# THREE_PHASE_METER.net
KiCad netlist of a schematic drawn in Altium Designer
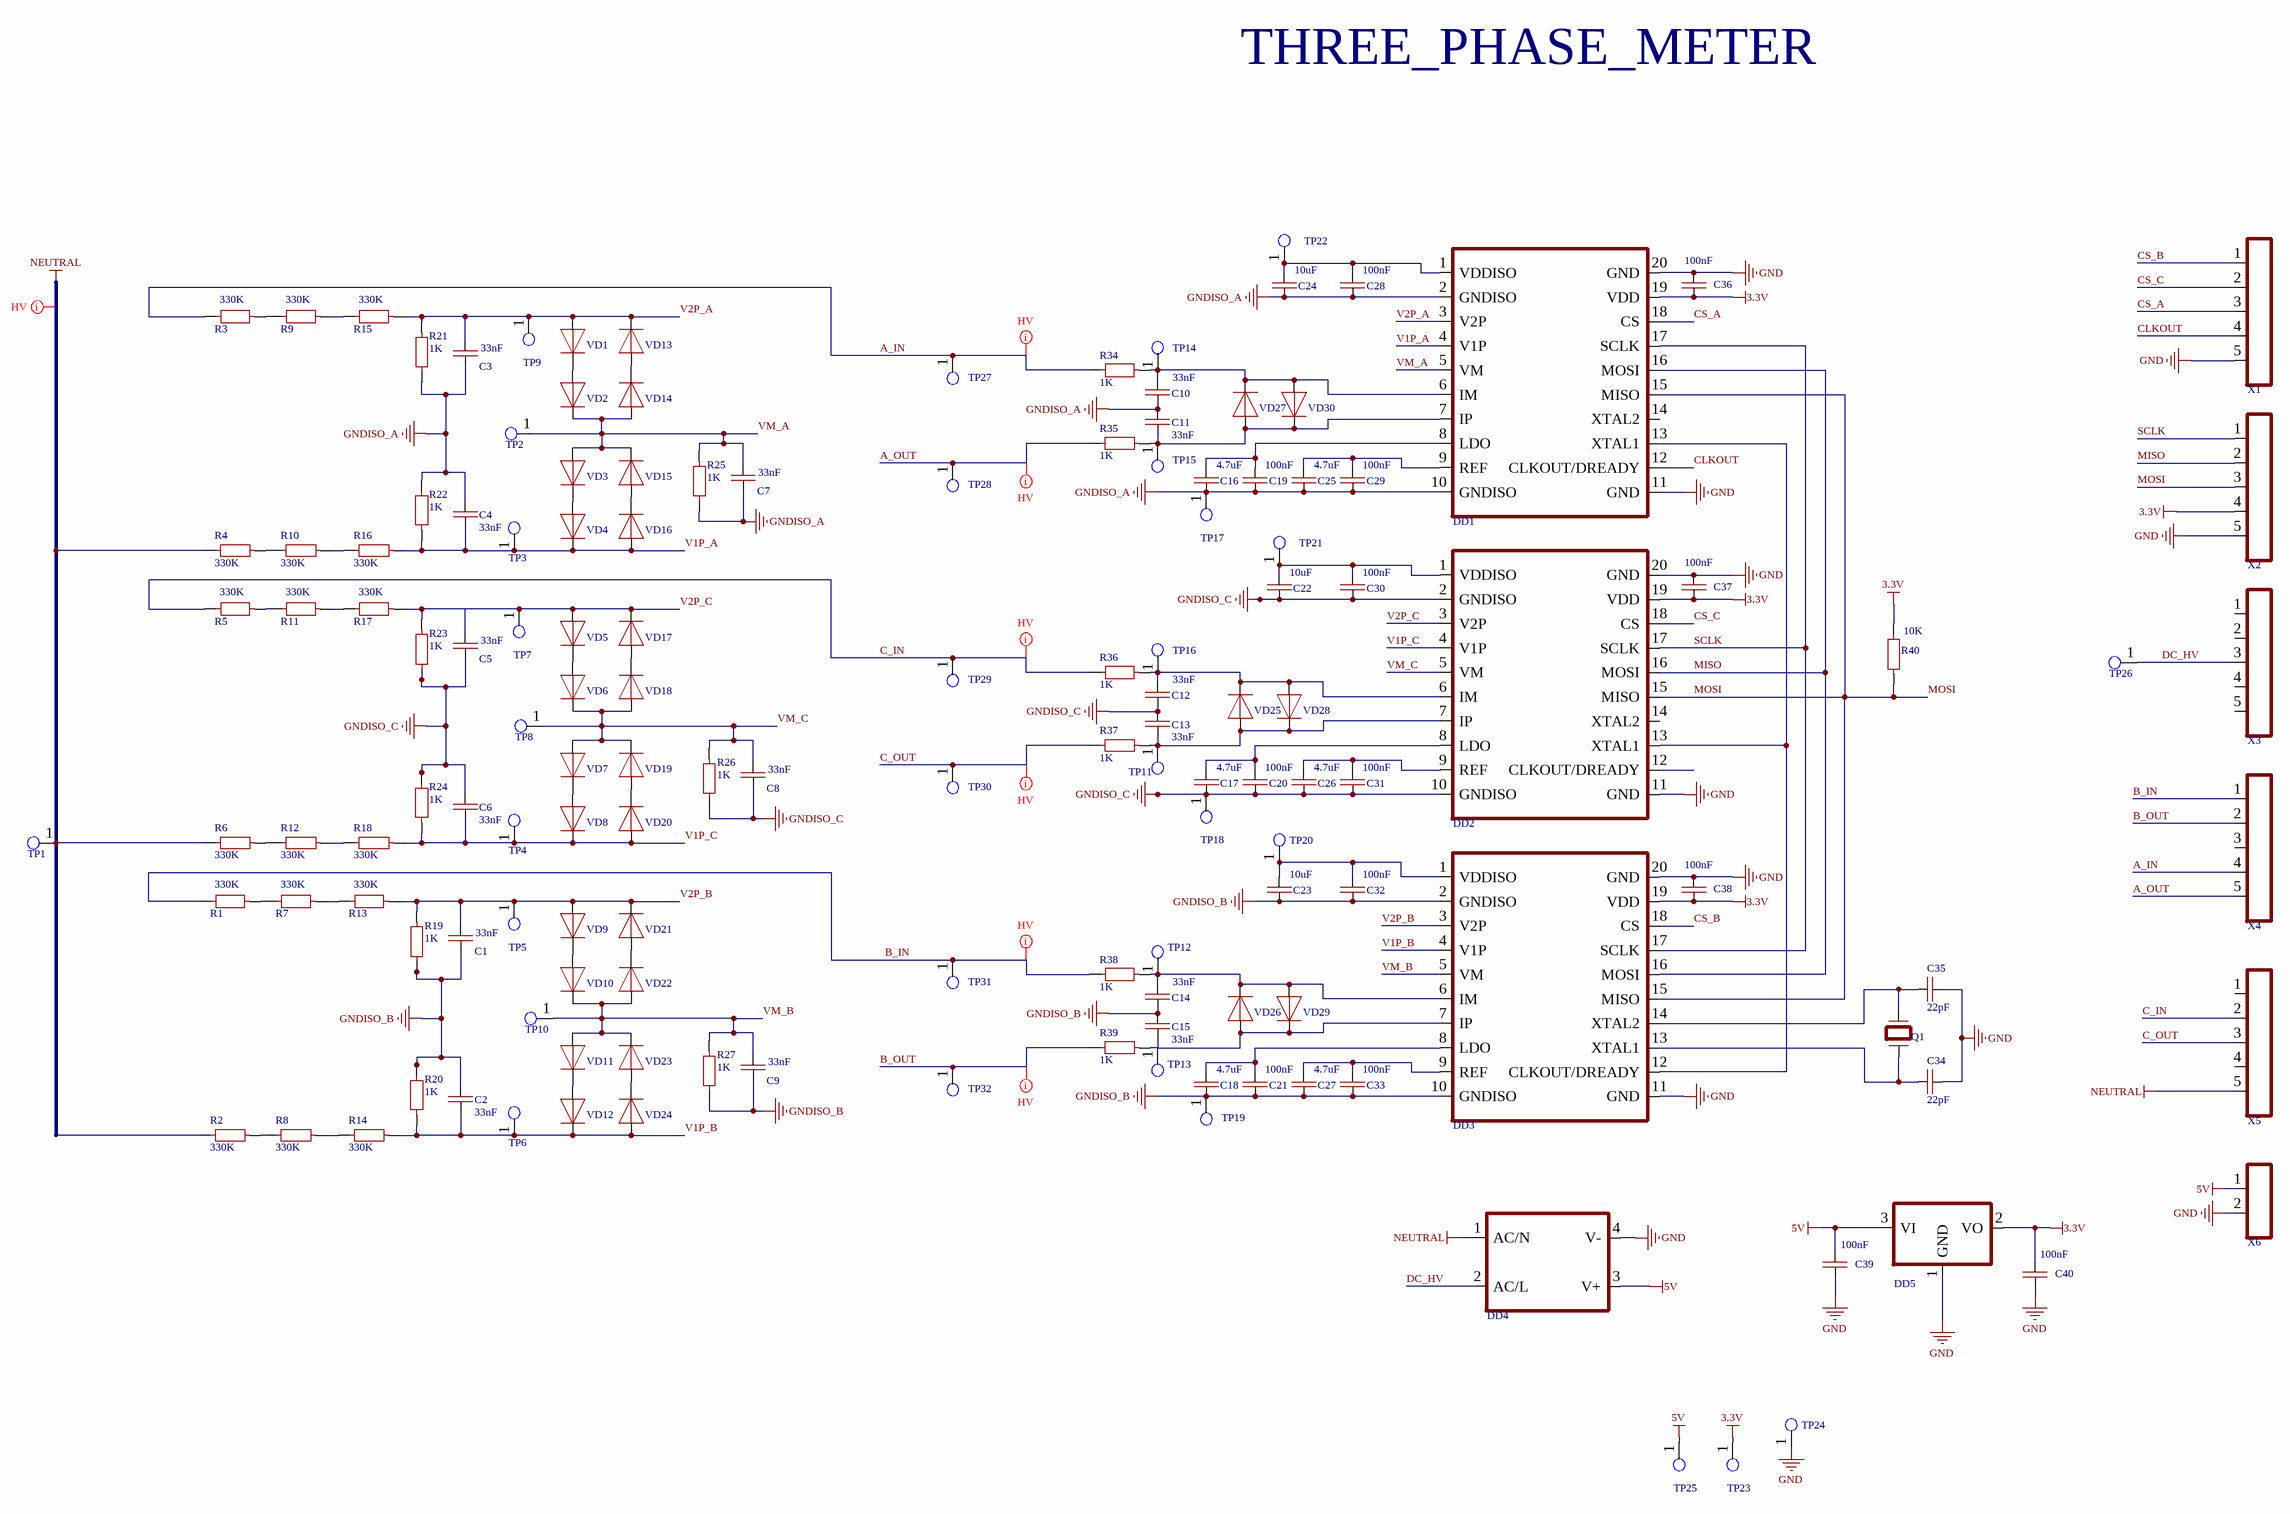
[diagram p0: THREE_PHASE_METER.SchDoc]

(export (version "E")
  (design (tool "Eeschema 10.0.6"))
  (components
    (comp (ref "C1")
      (value "33nF")
      (footprint "CAP-1206")
      (libsource (lib "PASSIVE_COMPONENTS") (part "CAP-NON-POLAR"))
    )
    (comp (ref "C2")
      (value "33nF")
      (footprint "CAP-1206")
      (libsource (lib "PASSIVE_COMPONENTS") (part "CAP-NON-POLAR"))
    )
    (comp (ref "C3")
      (value "33nF")
      (footprint "CAP-1206")
      (libsource (lib "PASSIVE_COMPONENTS") (part "CAP-NON-POLAR"))
    )
    (comp (ref "C4")
      (value "33nF")
      (footprint "CAP-1206")
      (libsource (lib "PASSIVE_COMPONENTS") (part "CAP-NON-POLAR"))
    )
    (comp (ref "C5")
      (value "33nF")
      (footprint "CAP-1206")
      (libsource (lib "PASSIVE_COMPONENTS") (part "CAP-NON-POLAR"))
    )
    (comp (ref "C6")
      (value "33nF")
      (footprint "CAP-1206")
      (libsource (lib "PASSIVE_COMPONENTS") (part "CAP-NON-POLAR"))
    )
    (comp (ref "C7")
      (value "33nF")
      (footprint "CAP-1206")
      (libsource (lib "PASSIVE_COMPONENTS") (part "CAP-NON-POLAR"))
    )
    (comp (ref "C8")
      (value "33nF")
      (footprint "CAP-1206")
      (libsource (lib "PASSIVE_COMPONENTS") (part "CAP-NON-POLAR"))
    )
    (comp (ref "C9")
      (value "33nF")
      (footprint "CAP-1206")
      (libsource (lib "PASSIVE_COMPONENTS") (part "CAP-NON-POLAR"))
    )
    (comp (ref "C10")
      (value "33nF")
      (footprint "CAP-1206")
      (libsource (lib "PASSIVE_COMPONENTS") (part "CAP-NON-POLAR"))
    )
    (comp (ref "C11")
      (value "33nF")
      (footprint "CAP-1206")
      (libsource (lib "PASSIVE_COMPONENTS") (part "CAP-NON-POLAR"))
    )
    (comp (ref "C12")
      (value "33nF")
      (footprint "CAP-1206")
      (libsource (lib "PASSIVE_COMPONENTS") (part "CAP-NON-POLAR"))
    )
    (comp (ref "C13")
      (value "33nF")
      (footprint "CAP-1206")
      (libsource (lib "PASSIVE_COMPONENTS") (part "CAP-NON-POLAR"))
    )
    (comp (ref "C14")
      (value "33nF")
      (footprint "CAP-1206")
      (libsource (lib "PASSIVE_COMPONENTS") (part "CAP-NON-POLAR"))
    )
    (comp (ref "C15")
      (value "33nF")
      (footprint "CAP-1206")
      (libsource (lib "PASSIVE_COMPONENTS") (part "CAP-NON-POLAR"))
    )
    (comp (ref "C16")
      (value "4.7uF")
      (footprint "CAP-1206")
      (libsource (lib "PASSIVE_COMPONENTS") (part "CAP-NON-POLAR"))
    )
    (comp (ref "C17")
      (value "4.7uF")
      (footprint "CAP-1206")
      (libsource (lib "PASSIVE_COMPONENTS") (part "CAP-NON-POLAR"))
    )
    (comp (ref "C18")
      (value "4.7uF")
      (footprint "CAP-1206")
      (libsource (lib "PASSIVE_COMPONENTS") (part "CAP-NON-POLAR"))
    )
    (comp (ref "C19")
      (value "100nF")
      (footprint "CAP-0603")
      (libsource (lib "PASSIVE_COMPONENTS") (part "CAP-NON-POLAR"))
    )
    (comp (ref "C20")
      (value "100nF")
      (footprint "CAP-0603")
      (libsource (lib "PASSIVE_COMPONENTS") (part "CAP-NON-POLAR"))
    )
    (comp (ref "C21")
      (value "100nF")
      (footprint "CAP-0603")
      (libsource (lib "PASSIVE_COMPONENTS") (part "CAP-NON-POLAR"))
    )
    (comp (ref "C22")
      (value "10uF")
      (footprint "CAP-1206")
      (libsource (lib "PASSIVE_COMPONENTS") (part "CAP-NON-POLAR"))
    )
    (comp (ref "C23")
      (value "10uF")
      (footprint "CAP-1206")
      (libsource (lib "PASSIVE_COMPONENTS") (part "CAP-NON-POLAR"))
    )
    (comp (ref "C24")
      (value "10uF")
      (footprint "CAP-1206")
      (libsource (lib "PASSIVE_COMPONENTS") (part "CAP-NON-POLAR"))
    )
    (comp (ref "C25")
      (value "4.7uF")
      (footprint "CAP-1206")
      (libsource (lib "PASSIVE_COMPONENTS") (part "CAP-NON-POLAR"))
    )
    (comp (ref "C26")
      (value "4.7uF")
      (footprint "CAP-1206")
      (libsource (lib "PASSIVE_COMPONENTS") (part "CAP-NON-POLAR"))
    )
    (comp (ref "C27")
      (value "4.7uF")
      (footprint "CAP-1206")
      (libsource (lib "PASSIVE_COMPONENTS") (part "CAP-NON-POLAR"))
    )
    (comp (ref "C28")
      (value "100nF")
      (footprint "CAP-0603")
      (libsource (lib "PASSIVE_COMPONENTS") (part "CAP-NON-POLAR"))
    )
    (comp (ref "C29")
      (value "100nF")
      (footprint "CAP-0603")
      (libsource (lib "PASSIVE_COMPONENTS") (part "CAP-NON-POLAR"))
    )
    (comp (ref "C30")
      (value "100nF")
      (footprint "CAP-0603")
      (libsource (lib "PASSIVE_COMPONENTS") (part "CAP-NON-POLAR"))
    )
    (comp (ref "C31")
      (value "100nF")
      (footprint "CAP-0603")
      (libsource (lib "PASSIVE_COMPONENTS") (part "CAP-NON-POLAR"))
    )
    (comp (ref "C32")
      (value "100nF")
      (footprint "CAP-0603")
      (libsource (lib "PASSIVE_COMPONENTS") (part "CAP-NON-POLAR"))
    )
    (comp (ref "C33")
      (value "100nF")
      (footprint "CAP-0603")
      (libsource (lib "PASSIVE_COMPONENTS") (part "CAP-NON-POLAR"))
    )
    (comp (ref "C34")
      (value "22pF")
      (footprint "CAP-0603")
      (libsource (lib "PASSIVE_COMPONENTS") (part "CAP-NON-POLAR"))
    )
    (comp (ref "C35")
      (value "22pF")
      (footprint "CAP-0603")
      (libsource (lib "PASSIVE_COMPONENTS") (part "CAP-NON-POLAR"))
    )
    (comp (ref "C36")
      (value "100nF")
      (footprint "CAP-0603")
      (libsource (lib "PASSIVE_COMPONENTS") (part "CAP-NON-POLAR"))
    )
    (comp (ref "C37")
      (value "100nF")
      (footprint "CAP-0603")
      (libsource (lib "PASSIVE_COMPONENTS") (part "CAP-NON-POLAR"))
    )
    (comp (ref "C38")
      (value "100nF")
      (footprint "CAP-0603")
      (libsource (lib "PASSIVE_COMPONENTS") (part "CAP-NON-POLAR"))
    )
    (comp (ref "C39")
      (value "100nF")
      (footprint "CAP-0603")
      (libsource (lib "PASSIVE_COMPONENTS") (part "CAP-NON-POLAR"))
    )
    (comp (ref "C40")
      (value "100nF")
      (footprint "CAP-0603")
      (libsource (lib "PASSIVE_COMPONENTS") (part "CAP-NON-POLAR"))
    )
    (comp (ref "DD1") (value "ADE7913") (footprint "SOIC20") (libsource (lib "ADE7913") (part "ADE7913")))
    (comp (ref "DD2") (value "ADE7913") (footprint "SOIC20") (libsource (lib "ADE7913") (part "ADE7913")))
    (comp (ref "DD3") (value "ADE7913") (footprint "SOIC20") (libsource (lib "ADE7913") (part "ADE7913")))
    (comp (ref "DD4") (value "IRM-01") (footprint "IRM-01") (libsource (lib "IRM-01") (part "IRM-01")))
    (comp (ref "DD5") (value "AMS1117") (footprint "SOT-223-3") (libsource (lib "AMS1117") (part "AMS1117")))
    (comp (ref "Q1")
      (value "OSC-2-PIN")
      (footprint "OSC-QSMD12.3x4.5x4.2")
      (libsource (lib "PASSIVE_COMPONENTS") (part "OSC-2-PIN"))
    )
    (comp (ref "R1")
      (value "330K")
      (footprint "RES-1206")
      (libsource (lib "PASSIVE_COMPONENTS") (part "RES-CONST"))
    )
    (comp (ref "R2")
      (value "330K")
      (footprint "RES-1206")
      (libsource (lib "PASSIVE_COMPONENTS") (part "RES-CONST"))
    )
    (comp (ref "R3")
      (value "330K")
      (footprint "RES-1206")
      (libsource (lib "PASSIVE_COMPONENTS") (part "RES-CONST"))
    )
    (comp (ref "R4")
      (value "330K")
      (footprint "RES-1206")
      (libsource (lib "PASSIVE_COMPONENTS") (part "RES-CONST"))
    )
    (comp (ref "R5")
      (value "330K")
      (footprint "RES-1206")
      (libsource (lib "PASSIVE_COMPONENTS") (part "RES-CONST"))
    )
    (comp (ref "R6")
      (value "330K")
      (footprint "RES-1206")
      (libsource (lib "PASSIVE_COMPONENTS") (part "RES-CONST"))
    )
    (comp (ref "R7")
      (value "330K")
      (footprint "RES-1206")
      (libsource (lib "PASSIVE_COMPONENTS") (part "RES-CONST"))
    )
    (comp (ref "R8")
      (value "330K")
      (footprint "RES-1206")
      (libsource (lib "PASSIVE_COMPONENTS") (part "RES-CONST"))
    )
    (comp (ref "R9")
      (value "330K")
      (footprint "RES-1206")
      (libsource (lib "PASSIVE_COMPONENTS") (part "RES-CONST"))
    )
    (comp (ref "R10")
      (value "330K")
      (footprint "RES-1206")
      (libsource (lib "PASSIVE_COMPONENTS") (part "RES-CONST"))
    )
    (comp (ref "R11")
      (value "330K")
      (footprint "RES-1206")
      (libsource (lib "PASSIVE_COMPONENTS") (part "RES-CONST"))
    )
    (comp (ref "R12")
      (value "330K")
      (footprint "RES-1206")
      (libsource (lib "PASSIVE_COMPONENTS") (part "RES-CONST"))
    )
    (comp (ref "R13")
      (value "330K")
      (footprint "RES-1206")
      (libsource (lib "PASSIVE_COMPONENTS") (part "RES-CONST"))
    )
    (comp (ref "R14")
      (value "330K")
      (footprint "RES-1206")
      (libsource (lib "PASSIVE_COMPONENTS") (part "RES-CONST"))
    )
    (comp (ref "R15")
      (value "330K")
      (footprint "RES-1206")
      (libsource (lib "PASSIVE_COMPONENTS") (part "RES-CONST"))
    )
    (comp (ref "R16")
      (value "330K")
      (footprint "RES-1206")
      (libsource (lib "PASSIVE_COMPONENTS") (part "RES-CONST"))
    )
    (comp (ref "R17")
      (value "330K")
      (footprint "RES-1206")
      (libsource (lib "PASSIVE_COMPONENTS") (part "RES-CONST"))
    )
    (comp (ref "R18")
      (value "330K")
      (footprint "RES-1206")
      (libsource (lib "PASSIVE_COMPONENTS") (part "RES-CONST"))
    )
    (comp (ref "R19")
      (value "1K")
      (footprint "RES-1206")
      (libsource (lib "PASSIVE_COMPONENTS") (part "RES-CONST"))
    )
    (comp (ref "R20")
      (value "1K")
      (footprint "RES-1206")
      (libsource (lib "PASSIVE_COMPONENTS") (part "RES-CONST"))
    )
    (comp (ref "R21")
      (value "1K")
      (footprint "RES-1206")
      (libsource (lib "PASSIVE_COMPONENTS") (part "RES-CONST"))
    )
    (comp (ref "R22")
      (value "1K")
      (footprint "RES-1206")
      (libsource (lib "PASSIVE_COMPONENTS") (part "RES-CONST"))
    )
    (comp (ref "R23")
      (value "1K")
      (footprint "RES-1206")
      (libsource (lib "PASSIVE_COMPONENTS") (part "RES-CONST"))
    )
    (comp (ref "R24")
      (value "1K")
      (footprint "RES-1206")
      (libsource (lib "PASSIVE_COMPONENTS") (part "RES-CONST"))
    )
    (comp (ref "R25")
      (value "1K")
      (footprint "RES-1206")
      (libsource (lib "PASSIVE_COMPONENTS") (part "RES-CONST"))
    )
    (comp (ref "R26")
      (value "1K")
      (footprint "RES-1206")
      (libsource (lib "PASSIVE_COMPONENTS") (part "RES-CONST"))
    )
    (comp (ref "R27")
      (value "1K")
      (footprint "RES-1206")
      (libsource (lib "PASSIVE_COMPONENTS") (part "RES-CONST"))
    )
    (comp (ref "R34")
      (value "1K")
      (footprint "RES-1206")
      (libsource (lib "PASSIVE_COMPONENTS") (part "RES-CONST"))
    )
    (comp (ref "R35")
      (value "1K")
      (footprint "RES-1206")
      (libsource (lib "PASSIVE_COMPONENTS") (part "RES-CONST"))
    )
    (comp (ref "R36")
      (value "1K")
      (footprint "RES-1206")
      (libsource (lib "PASSIVE_COMPONENTS") (part "RES-CONST"))
    )
    (comp (ref "R37")
      (value "1K")
      (footprint "RES-1206")
      (libsource (lib "PASSIVE_COMPONENTS") (part "RES-CONST"))
    )
    (comp (ref "R38")
      (value "1K")
      (footprint "RES-1206")
      (libsource (lib "PASSIVE_COMPONENTS") (part "RES-CONST"))
    )
    (comp (ref "R39")
      (value "1K")
      (footprint "RES-1206")
      (libsource (lib "PASSIVE_COMPONENTS") (part "RES-CONST"))
    )
    (comp (ref "R40")
      (value "10K")
      (footprint "RES-0603")
      (libsource (lib "PASSIVE_COMPONENTS") (part "RES-CONST"))
    )
    (comp (ref "TP1")
      (value "Test_Point_PCB")
      (footprint "Test_Point")
      (description "Test_Point")
      (libsource (lib "Test_Point") (part "TP_PCB?"))
    )
    (comp (ref "TP2")
      (value "Test_Point_PCB")
      (footprint "Test_Point")
      (description "Test_Point")
      (libsource (lib "Test_Point") (part "TP_PCB?"))
    )
    (comp (ref "TP3")
      (value "Test_Point_PCB")
      (footprint "Test_Point")
      (description "Test_Point")
      (libsource (lib "Test_Point") (part "TP_PCB?"))
    )
    (comp (ref "TP4")
      (value "Test_Point_PCB")
      (footprint "Test_Point")
      (description "Test_Point")
      (libsource (lib "Test_Point") (part "TP_PCB?"))
    )
    (comp (ref "TP5")
      (value "Test_Point_PCB")
      (footprint "Test_Point")
      (description "Test_Point")
      (libsource (lib "Test_Point") (part "TP_PCB?"))
    )
    (comp (ref "TP6")
      (value "Test_Point_PCB")
      (footprint "Test_Point")
      (description "Test_Point")
      (libsource (lib "Test_Point") (part "TP_PCB?"))
    )
    (comp (ref "TP7")
      (value "Test_Point_PCB")
      (footprint "Test_Point")
      (description "Test_Point")
      (libsource (lib "Test_Point") (part "TP_PCB?"))
    )
    (comp (ref "TP8")
      (value "Test_Point_PCB")
      (footprint "Test_Point")
      (description "Test_Point")
      (libsource (lib "Test_Point") (part "TP_PCB?"))
    )
    (comp (ref "TP9")
      (value "Test_Point_PCB")
      (footprint "Test_Point")
      (description "Test_Point")
      (libsource (lib "Test_Point") (part "TP_PCB?"))
    )
    (comp (ref "TP10")
      (value "Test_Point_PCB")
      (footprint "Test_Point")
      (description "Test_Point")
      (libsource (lib "Test_Point") (part "TP_PCB?"))
    )
    (comp (ref "TP11")
      (value "Test_Point_PCB")
      (footprint "Test_Point")
      (description "Test_Point")
      (libsource (lib "Test_Point") (part "TP_PCB?"))
    )
    (comp (ref "TP12")
      (value "Test_Point_PCB")
      (footprint "Test_Point")
      (description "Test_Point")
      (libsource (lib "Test_Point") (part "TP_PCB?"))
    )
    (comp (ref "TP13")
      (value "Test_Point_PCB")
      (footprint "Test_Point")
      (description "Test_Point")
      (libsource (lib "Test_Point") (part "TP_PCB?"))
    )
    (comp (ref "TP14")
      (value "Test_Point_PCB")
      (footprint "Test_Point")
      (description "Test_Point")
      (libsource (lib "Test_Point") (part "TP_PCB?"))
    )
    (comp (ref "TP15")
      (value "Test_Point_PCB")
      (footprint "Test_Point")
      (description "Test_Point")
      (libsource (lib "Test_Point") (part "TP_PCB?"))
    )
    (comp (ref "TP16")
      (value "Test_Point_PCB")
      (footprint "Test_Point")
      (description "Test_Point")
      (libsource (lib "Test_Point") (part "TP_PCB?"))
    )
    (comp (ref "TP17")
      (value "Test_Point_PCB")
      (footprint "Test_Point")
      (description "Test_Point")
      (libsource (lib "Test_Point") (part "TP_PCB?"))
    )
    (comp (ref "TP18")
      (value "Test_Point_PCB")
      (footprint "Test_Point")
      (description "Test_Point")
      (libsource (lib "Test_Point") (part "TP_PCB?"))
    )
    (comp (ref "TP19")
      (value "Test_Point_PCB")
      (footprint "Test_Point")
      (description "Test_Point")
      (libsource (lib "Test_Point") (part "TP_PCB?"))
    )
    (comp (ref "TP20")
      (value "Test_Point_PCB")
      (footprint "Test_Point")
      (description "Test_Point")
      (libsource (lib "Test_Point") (part "TP_PCB?"))
    )
    (comp (ref "TP21")
      (value "Test_Point_PCB")
      (footprint "Test_Point")
      (description "Test_Point")
      (libsource (lib "Test_Point") (part "TP_PCB?"))
    )
    (comp (ref "TP22")
      (value "Test_Point_PCB")
      (footprint "Test_Point")
      (description "Test_Point")
      (libsource (lib "Test_Point") (part "TP_PCB?"))
    )
    (comp (ref "TP23")
      (value "Test_Point_PCB")
      (footprint "Test_Point")
      (description "Test_Point")
      (libsource (lib "Test_Point") (part "TP_PCB?"))
    )
    (comp (ref "TP24")
      (value "Test_Point_PCB")
      (footprint "Test_Point")
      (description "Test_Point")
      (libsource (lib "Test_Point") (part "TP_PCB?"))
    )
    (comp (ref "TP25")
      (value "Test_Point_PCB")
      (footprint "Test_Point")
      (description "Test_Point")
      (libsource (lib "Test_Point") (part "TP_PCB?"))
    )
    (comp (ref "TP26")
      (value "Test_Point_PCB")
      (footprint "Test_Point")
      (description "Test_Point")
      (libsource (lib "Test_Point") (part "TP_PCB?"))
    )
    (comp (ref "TP27")
      (value "Test_Point_PCB")
      (footprint "Test_Point")
      (description "Test_Point")
      (libsource (lib "Test_Point") (part "TP_PCB?"))
    )
    (comp (ref "TP28")
      (value "Test_Point_PCB")
      (footprint "Test_Point")
      (description "Test_Point")
      (libsource (lib "Test_Point") (part "TP_PCB?"))
    )
    (comp (ref "TP29")
      (value "Test_Point_PCB")
      (footprint "Test_Point")
      (description "Test_Point")
      (libsource (lib "Test_Point") (part "TP_PCB?"))
    )
    (comp (ref "TP30")
      (value "Test_Point_PCB")
      (footprint "Test_Point")
      (description "Test_Point")
      (libsource (lib "Test_Point") (part "TP_PCB?"))
    )
    (comp (ref "TP31")
      (value "Test_Point_PCB")
      (footprint "Test_Point")
      (description "Test_Point")
      (libsource (lib "Test_Point") (part "TP_PCB?"))
    )
    (comp (ref "TP32")
      (value "Test_Point_PCB")
      (footprint "Test_Point")
      (description "Test_Point")
      (libsource (lib "Test_Point") (part "TP_PCB?"))
    )
    (comp (ref "VD1")
      (value "DIODE")
      (footprint "DIODE-0805")
      (libsource (lib "PASSIVE_COMPONENTS") (part "DIODE"))
    )
    (comp (ref "VD2")
      (value "DIODE")
      (footprint "DIODE-0805")
      (libsource (lib "PASSIVE_COMPONENTS") (part "DIODE"))
    )
    (comp (ref "VD3")
      (value "DIODE")
      (footprint "DIODE-0805")
      (libsource (lib "PASSIVE_COMPONENTS") (part "DIODE"))
    )
    (comp (ref "VD4")
      (value "DIODE")
      (footprint "DIODE-0805")
      (libsource (lib "PASSIVE_COMPONENTS") (part "DIODE"))
    )
    (comp (ref "VD5")
      (value "DIODE")
      (footprint "DIODE-0805")
      (libsource (lib "PASSIVE_COMPONENTS") (part "DIODE"))
    )
    (comp (ref "VD6")
      (value "DIODE")
      (footprint "DIODE-0805")
      (libsource (lib "PASSIVE_COMPONENTS") (part "DIODE"))
    )
    (comp (ref "VD7")
      (value "DIODE")
      (footprint "DIODE-0805")
      (libsource (lib "PASSIVE_COMPONENTS") (part "DIODE"))
    )
    (comp (ref "VD8")
      (value "DIODE")
      (footprint "DIODE-0805")
      (libsource (lib "PASSIVE_COMPONENTS") (part "DIODE"))
    )
    (comp (ref "VD9")
      (value "DIODE")
      (footprint "DIODE-0805")
      (libsource (lib "PASSIVE_COMPONENTS") (part "DIODE"))
    )
    (comp (ref "VD10")
      (value "DIODE")
      (footprint "DIODE-0805")
      (libsource (lib "PASSIVE_COMPONENTS") (part "DIODE"))
    )
    (comp (ref "VD11")
      (value "DIODE")
      (footprint "DIODE-0805")
      (libsource (lib "PASSIVE_COMPONENTS") (part "DIODE"))
    )
    (comp (ref "VD12")
      (value "DIODE")
      (footprint "DIODE-0805")
      (libsource (lib "PASSIVE_COMPONENTS") (part "DIODE"))
    )
    (comp (ref "VD13")
      (value "DIODE")
      (footprint "DIODE-0805")
      (libsource (lib "PASSIVE_COMPONENTS") (part "DIODE"))
    )
    (comp (ref "VD14")
      (value "DIODE")
      (footprint "DIODE-0805")
      (libsource (lib "PASSIVE_COMPONENTS") (part "DIODE"))
    )
    (comp (ref "VD15")
      (value "DIODE")
      (footprint "DIODE-0805")
      (libsource (lib "PASSIVE_COMPONENTS") (part "DIODE"))
    )
    (comp (ref "VD16")
      (value "DIODE")
      (footprint "DIODE-0805")
      (libsource (lib "PASSIVE_COMPONENTS") (part "DIODE"))
    )
    (comp (ref "VD17")
      (value "DIODE")
      (footprint "DIODE-0805")
      (libsource (lib "PASSIVE_COMPONENTS") (part "DIODE"))
    )
    (comp (ref "VD18")
      (value "DIODE")
      (footprint "DIODE-0805")
      (libsource (lib "PASSIVE_COMPONENTS") (part "DIODE"))
    )
    (comp (ref "VD19")
      (value "DIODE")
      (footprint "DIODE-0805")
      (libsource (lib "PASSIVE_COMPONENTS") (part "DIODE"))
    )
    (comp (ref "VD20")
      (value "DIODE")
      (footprint "DIODE-0805")
      (libsource (lib "PASSIVE_COMPONENTS") (part "DIODE"))
    )
    (comp (ref "VD21")
      (value "DIODE")
      (footprint "DIODE-0805")
      (libsource (lib "PASSIVE_COMPONENTS") (part "DIODE"))
    )
    (comp (ref "VD22")
      (value "DIODE")
      (footprint "DIODE-0805")
      (libsource (lib "PASSIVE_COMPONENTS") (part "DIODE"))
    )
    (comp (ref "VD23")
      (value "DIODE")
      (footprint "DIODE-0805")
      (libsource (lib "PASSIVE_COMPONENTS") (part "DIODE"))
    )
    (comp (ref "VD24")
      (value "DIODE")
      (footprint "DIODE-0805")
      (libsource (lib "PASSIVE_COMPONENTS") (part "DIODE"))
    )
    (comp (ref "VD25")
      (value "DIODE")
      (footprint "DIODE-0805")
      (libsource (lib "PASSIVE_COMPONENTS") (part "DIODE"))
    )
    (comp (ref "VD26")
      (value "DIODE")
      (footprint "DIODE-0805")
      (libsource (lib "PASSIVE_COMPONENTS") (part "DIODE"))
    )
    (comp (ref "VD27")
      (value "DIODE")
      (footprint "DIODE-0805")
      (libsource (lib "PASSIVE_COMPONENTS") (part "DIODE"))
    )
    (comp (ref "VD28")
      (value "DIODE")
      (footprint "DIODE-0805")
      (libsource (lib "PASSIVE_COMPONENTS") (part "DIODE"))
    )
    (comp (ref "VD29")
      (value "DIODE")
      (footprint "DIODE-0805")
      (libsource (lib "PASSIVE_COMPONENTS") (part "DIODE"))
    )
    (comp (ref "VD30")
      (value "DIODE")
      (footprint "DIODE-0805")
      (libsource (lib "PASSIVE_COMPONENTS") (part "DIODE"))
    )
    (comp (ref "X1")
      (value "CONN-5-PIN")
      (footprint "CONN-PLS-5-2.54mm")
      (libsource (lib "CONNECTORS") (part "CONN-5-PIN"))
    )
    (comp (ref "X2")
      (value "CONN-5-PIN")
      (footprint "CONN-PLS-5-2.54mm")
      (libsource (lib "CONNECTORS") (part "CONN-5-PIN"))
    )
    (comp (ref "X3")
      (value "CONN-5-PIN")
      (footprint "CONN-PLS-5-2.54mm")
      (libsource (lib "CONNECTORS") (part "CONN-5-PIN"))
    )
    (comp (ref "X4")
      (value "CONN-5-PIN")
      (footprint "CONN-PLS-5-2.54mm")
      (libsource (lib "CONNECTORS") (part "CONN-5-PIN"))
    )
    (comp (ref "X5")
      (value "CONN-5-PIN")
      (footprint "CONN-PLS-5-2.54mm")
      (libsource (lib "CONNECTORS") (part "CONN-5-PIN"))
    )
    (comp (ref "X6")
      (value "CONN-2-PIN")
      (footprint "CONN-PLS-2-2.54mm")
      (libsource (lib "CONN-2-PIN") (part "CONN-2-PIN"))
    )
  )
  (nets
    (net (code "1") (name "/A_IN") (class "Default")
      (node (ref "R3") (pin "2") (pinfunction "2_2") (pintype "passive"))
      (node (ref "R34") (pin "2") (pinfunction "2_2") (pintype "passive"))
      (node (ref "TP27") (pin "1") (pinfunction "G9_1") (pintype "passive"))
      (node (ref "X4") (pin "4") (pinfunction "4_4") (pintype "passive"))
    )
    (net (code "2") (name "/A_OUT") (class "Default")
      (node (ref "R35") (pin "2") (pinfunction "2_2") (pintype "passive"))
      (node (ref "TP28") (pin "1") (pinfunction "G9_1") (pintype "passive"))
      (node (ref "X4") (pin "5") (pinfunction "5_5") (pintype "passive"))
    )
    (net (code "3") (name "/B_IN") (class "Default")
      (node (ref "R1") (pin "2") (pinfunction "2_2") (pintype "passive"))
      (node (ref "R38") (pin "2") (pinfunction "2_2") (pintype "passive"))
      (node (ref "TP31") (pin "1") (pinfunction "G9_1") (pintype "passive"))
      (node (ref "X4") (pin "1") (pinfunction "1_1") (pintype "passive"))
    )
    (net (code "4") (name "/B_OUT") (class "Default")
      (node (ref "R39") (pin "2") (pinfunction "2_2") (pintype "passive"))
      (node (ref "TP32") (pin "1") (pinfunction "G9_1") (pintype "passive"))
      (node (ref "X4") (pin "2") (pinfunction "2_2") (pintype "passive"))
    )
    (net (code "5") (name "/CLKOUT") (class "Default")
      (node (ref "DD1") (pin "12") (pinfunction "CLKOUT/DREADY_12") (pintype "passive"))
      (node (ref "X1") (pin "4") (pinfunction "4_4") (pintype "passive"))
    )
    (net (code "6") (name "/CS_A") (class "Default")
      (node (ref "DD1") (pin "18") (pinfunction "CS_18") (pintype "passive"))
      (node (ref "X1") (pin "3") (pinfunction "3_3") (pintype "passive"))
    )
    (net (code "7") (name "/CS_B") (class "Default")
      (node (ref "DD3") (pin "18") (pinfunction "CS_18") (pintype "passive"))
      (node (ref "X1") (pin "1") (pinfunction "1_1") (pintype "passive"))
    )
    (net (code "8") (name "/CS_C") (class "Default")
      (node (ref "DD2") (pin "18") (pinfunction "CS_18") (pintype "passive"))
      (node (ref "X1") (pin "2") (pinfunction "2_2") (pintype "passive"))
    )
    (net (code "9") (name "/C_IN") (class "Default")
      (node (ref "R36") (pin "2") (pinfunction "2_2") (pintype "passive"))
      (node (ref "R5") (pin "2") (pinfunction "2_2") (pintype "passive"))
      (node (ref "TP29") (pin "1") (pinfunction "G9_1") (pintype "passive"))
      (node (ref "X5") (pin "2") (pinfunction "2_2") (pintype "passive"))
    )
    (net (code "10") (name "/C_OUT") (class "Default")
      (node (ref "R37") (pin "2") (pinfunction "2_2") (pintype "passive"))
      (node (ref "TP30") (pin "1") (pinfunction "G9_1") (pintype "passive"))
      (node (ref "X5") (pin "3") (pinfunction "3_3") (pintype "passive"))
    )
    (net (code "11") (name "/DC_HV") (class "Default")
      (node (ref "DD4") (pin "2") (pinfunction "AC/L_2") (pintype "passive"))
      (node (ref "TP26") (pin "1") (pinfunction "G9_1") (pintype "passive"))
      (node (ref "X3") (pin "3") (pinfunction "3_3") (pintype "passive"))
    )
    (net (code "12") (name "/MISO") (class "Default")
      (node (ref "DD1") (pin "16") (pinfunction "MOSI_16") (pintype "passive"))
      (node (ref "DD2") (pin "16") (pinfunction "MOSI_16") (pintype "passive"))
      (node (ref "DD3") (pin "16") (pinfunction "MOSI_16") (pintype "passive"))
      (node (ref "X2") (pin "2") (pinfunction "2_2") (pintype "passive"))
    )
    (net (code "13") (name "/MOSI") (class "Default")
      (node (ref "DD1") (pin "15") (pinfunction "MISO_15") (pintype "passive"))
      (node (ref "DD2") (pin "15") (pinfunction "MISO_15") (pintype "passive"))
      (node (ref "DD3") (pin "15") (pinfunction "MISO_15") (pintype "passive"))
      (node (ref "R40") (pin "1") (pinfunction "1_1") (pintype "passive"))
      (node (ref "X2") (pin "3") (pinfunction "3_3") (pintype "passive"))
    )
    (net (code "14") (name "/SCLK") (class "Default")
      (node (ref "DD1") (pin "17") (pinfunction "SCLK_17") (pintype "passive"))
      (node (ref "DD2") (pin "17") (pinfunction "SCLK_17") (pintype "passive"))
      (node (ref "DD3") (pin "17") (pinfunction "SCLK_17") (pintype "passive"))
      (node (ref "X2") (pin "1") (pinfunction "1_1") (pintype "passive"))
    )
    (net (code "15") (name "/V1P_A") (class "Default")
      (node (ref "C4") (pin "2") (pinfunction "2_2") (pintype "passive"))
      (node (ref "DD1") (pin "4") (pinfunction "V1P_4") (pintype "passive"))
      (node (ref "R16") (pin "1") (pinfunction "1_1") (pintype "passive"))
      (node (ref "R22") (pin "1") (pinfunction "1_1") (pintype "passive"))
      (node (ref "TP3") (pin "1") (pinfunction "G9_1") (pintype "passive"))
      (node (ref "VD16") (pin "2") (pinfunction "A_2") (pintype "passive"))
      (node (ref "VD4") (pin "1") (pinfunction "C_1") (pintype "passive"))
    )
    (net (code "16") (name "/V1P_B") (class "Default")
      (node (ref "C2") (pin "2") (pinfunction "2_2") (pintype "passive"))
      (node (ref "DD3") (pin "4") (pinfunction "V1P_4") (pintype "passive"))
      (node (ref "R14") (pin "1") (pinfunction "1_1") (pintype "passive"))
      (node (ref "R20") (pin "1") (pinfunction "1_1") (pintype "passive"))
      (node (ref "TP6") (pin "1") (pinfunction "G9_1") (pintype "passive"))
      (node (ref "VD12") (pin "1") (pinfunction "C_1") (pintype "passive"))
      (node (ref "VD24") (pin "2") (pinfunction "A_2") (pintype "passive"))
    )
    (net (code "17") (name "/V1P_C") (class "Default")
      (node (ref "C6") (pin "2") (pinfunction "2_2") (pintype "passive"))
      (node (ref "DD2") (pin "4") (pinfunction "V1P_4") (pintype "passive"))
      (node (ref "R18") (pin "1") (pinfunction "1_1") (pintype "passive"))
      (node (ref "R24") (pin "1") (pinfunction "1_1") (pintype "passive"))
      (node (ref "TP4") (pin "1") (pinfunction "G9_1") (pintype "passive"))
      (node (ref "VD20") (pin "2") (pinfunction "A_2") (pintype "passive"))
      (node (ref "VD8") (pin "1") (pinfunction "C_1") (pintype "passive"))
    )
    (net (code "18") (name "/V2P_A") (class "Default")
      (node (ref "C3") (pin "2") (pinfunction "2_2") (pintype "passive"))
      (node (ref "DD1") (pin "3") (pinfunction "V2P_3") (pintype "passive"))
      (node (ref "R15") (pin "1") (pinfunction "1_1") (pintype "passive"))
      (node (ref "R21") (pin "1") (pinfunction "1_1") (pintype "passive"))
      (node (ref "TP9") (pin "1") (pinfunction "G9_1") (pintype "passive"))
      (node (ref "VD1") (pin "2") (pinfunction "A_2") (pintype "passive"))
      (node (ref "VD13") (pin "1") (pinfunction "C_1") (pintype "passive"))
    )
    (net (code "19") (name "/V2P_B") (class "Default")
      (node (ref "C1") (pin "2") (pinfunction "2_2") (pintype "passive"))
      (node (ref "DD3") (pin "3") (pinfunction "V2P_3") (pintype "passive"))
      (node (ref "R13") (pin "1") (pinfunction "1_1") (pintype "passive"))
      (node (ref "R19") (pin "1") (pinfunction "1_1") (pintype "passive"))
      (node (ref "TP5") (pin "1") (pinfunction "G9_1") (pintype "passive"))
      (node (ref "VD21") (pin "1") (pinfunction "C_1") (pintype "passive"))
      (node (ref "VD9") (pin "2") (pinfunction "A_2") (pintype "passive"))
    )
    (net (code "20") (name "/V2P_C") (class "Default")
      (node (ref "C5") (pin "2") (pinfunction "2_2") (pintype "passive"))
      (node (ref "DD2") (pin "3") (pinfunction "V2P_3") (pintype "passive"))
      (node (ref "R17") (pin "1") (pinfunction "1_1") (pintype "passive"))
      (node (ref "R23") (pin "1") (pinfunction "1_1") (pintype "passive"))
      (node (ref "TP7") (pin "1") (pinfunction "G9_1") (pintype "passive"))
      (node (ref "VD17") (pin "1") (pinfunction "C_1") (pintype "passive"))
      (node (ref "VD5") (pin "2") (pinfunction "A_2") (pintype "passive"))
    )
    (net (code "21") (name "/VM_A") (class "Default")
      (node (ref "C7") (pin "2") (pinfunction "2_2") (pintype "passive"))
      (node (ref "DD1") (pin "5") (pinfunction "VM_5") (pintype "passive"))
      (node (ref "R25") (pin "1") (pinfunction "1_1") (pintype "passive"))
      (node (ref "TP2") (pin "1") (pinfunction "G9_1") (pintype "passive"))
      (node (ref "VD14") (pin "2") (pinfunction "A_2") (pintype "passive"))
      (node (ref "VD15") (pin "1") (pinfunction "C_1") (pintype "passive"))
      (node (ref "VD2") (pin "1") (pinfunction "C_1") (pintype "passive"))
      (node (ref "VD3") (pin "2") (pinfunction "A_2") (pintype "passive"))
    )
    (net (code "22") (name "/VM_B") (class "Default")
      (node (ref "C9") (pin "2") (pinfunction "2_2") (pintype "passive"))
      (node (ref "DD3") (pin "5") (pinfunction "VM_5") (pintype "passive"))
      (node (ref "R27") (pin "1") (pinfunction "1_1") (pintype "passive"))
      (node (ref "TP10") (pin "1") (pinfunction "G9_1") (pintype "passive"))
      (node (ref "VD10") (pin "1") (pinfunction "C_1") (pintype "passive"))
      (node (ref "VD11") (pin "2") (pinfunction "A_2") (pintype "passive"))
      (node (ref "VD22") (pin "2") (pinfunction "A_2") (pintype "passive"))
      (node (ref "VD23") (pin "1") (pinfunction "C_1") (pintype "passive"))
    )
    (net (code "23") (name "/VM_C") (class "Default")
      (node (ref "C8") (pin "2") (pinfunction "2_2") (pintype "passive"))
      (node (ref "DD2") (pin "5") (pinfunction "VM_5") (pintype "passive"))
      (node (ref "R26") (pin "1") (pinfunction "1_1") (pintype "passive"))
      (node (ref "TP8") (pin "1") (pinfunction "G9_1") (pintype "passive"))
      (node (ref "VD18") (pin "2") (pinfunction "A_2") (pintype "passive"))
      (node (ref "VD19") (pin "1") (pinfunction "C_1") (pintype "passive"))
      (node (ref "VD6") (pin "1") (pinfunction "C_1") (pintype "passive"))
      (node (ref "VD7") (pin "2") (pinfunction "A_2") (pintype "passive"))
    )
    (net (code "24") (name "3.3V") (class "Default")
      (node (ref "C36") (pin "1") (pinfunction "1_1") (pintype "passive"))
      (node (ref "C37") (pin "1") (pinfunction "1_1") (pintype "passive"))
      (node (ref "C38") (pin "1") (pinfunction "1_1") (pintype "passive"))
      (node (ref "C40") (pin "2") (pinfunction "2_2") (pintype "passive"))
      (node (ref "DD1") (pin "19") (pinfunction "VDD_19") (pintype "passive"))
      (node (ref "DD2") (pin "19") (pinfunction "VDD_19") (pintype "passive"))
      (node (ref "DD3") (pin "19") (pinfunction "VDD_19") (pintype "passive"))
      (node (ref "DD5") (pin "2") (pinfunction "VO_2") (pintype "passive"))
      (node (ref "R40") (pin "2") (pinfunction "2_2") (pintype "passive"))
      (node (ref "TP23") (pin "1") (pinfunction "G9_1") (pintype "passive"))
      (node (ref "X2") (pin "4") (pinfunction "4_4") (pintype "passive"))
    )
    (net (code "25") (name "5V") (class "Default")
      (node (ref "C39") (pin "2") (pinfunction "2_2") (pintype "passive"))
      (node (ref "DD4") (pin "3") (pinfunction "V+_3") (pintype "passive"))
      (node (ref "DD5") (pin "3") (pinfunction "VI_3") (pintype "passive"))
      (node (ref "TP25") (pin "1") (pinfunction "G9_1") (pintype "passive"))
      (node (ref "X6") (pin "1") (pinfunction "1_1") (pintype "passive"))
    )
    (net (code "26") (name "GND") (class "Default")
      (node (ref "C34") (pin "1") (pinfunction "1_1") (pintype "passive"))
      (node (ref "C35") (pin "1") (pinfunction "1_1") (pintype "passive"))
      (node (ref "C36") (pin "2") (pinfunction "2_2") (pintype "passive"))
      (node (ref "C37") (pin "2") (pinfunction "2_2") (pintype "passive"))
      (node (ref "C38") (pin "2") (pinfunction "2_2") (pintype "passive"))
      (node (ref "C39") (pin "1") (pinfunction "1_1") (pintype "passive"))
      (node (ref "C40") (pin "1") (pinfunction "1_1") (pintype "passive"))
      (node (ref "DD1") (pin "11") (pinfunction "GND_11") (pintype "passive"))
      (node (ref "DD1") (pin "20") (pinfunction "GND_20") (pintype "passive"))
      (node (ref "DD2") (pin "11") (pinfunction "GND_11") (pintype "passive"))
      (node (ref "DD2") (pin "20") (pinfunction "GND_20") (pintype "passive"))
      (node (ref "DD3") (pin "11") (pinfunction "GND_11") (pintype "passive"))
      (node (ref "DD3") (pin "20") (pinfunction "GND_20") (pintype "passive"))
      (node (ref "DD4") (pin "4") (pinfunction "V-_4") (pintype "passive"))
      (node (ref "DD5") (pin "1") (pinfunction "GND_1") (pintype "passive"))
      (node (ref "TP24") (pin "1") (pinfunction "G9_1") (pintype "passive"))
      (node (ref "X1") (pin "5") (pinfunction "5_5") (pintype "passive"))
      (node (ref "X2") (pin "5") (pinfunction "5_5") (pintype "passive"))
      (node (ref "X6") (pin "2") (pinfunction "2_2") (pintype "passive"))
    )
    (net (code "27") (name "GNDISO_A") (class "Default")
      (node (ref "C10") (pin "1") (pinfunction "1_1") (pintype "passive"))
      (node (ref "C11") (pin "1") (pinfunction "1_1") (pintype "passive"))
      (node (ref "C16") (pin "1") (pinfunction "1_1") (pintype "passive"))
      (node (ref "C19") (pin "1") (pinfunction "1_1") (pintype "passive"))
      (node (ref "C24") (pin "1") (pinfunction "1_1") (pintype "passive"))
      (node (ref "C25") (pin "1") (pinfunction "1_1") (pintype "passive"))
      (node (ref "C28") (pin "1") (pinfunction "1_1") (pintype "passive"))
      (node (ref "C29") (pin "1") (pinfunction "1_1") (pintype "passive"))
      (node (ref "C3") (pin "1") (pinfunction "1_1") (pintype "passive"))
      (node (ref "C4") (pin "1") (pinfunction "1_1") (pintype "passive"))
      (node (ref "C7") (pin "1") (pinfunction "1_1") (pintype "passive"))
      (node (ref "DD1") (pin "10") (pinfunction "GNDISO_10") (pintype "passive"))
      (node (ref "DD1") (pin "2") (pinfunction "GNDISO_2") (pintype "passive"))
      (node (ref "R21") (pin "2") (pinfunction "2_2") (pintype "passive"))
      (node (ref "R22") (pin "2") (pinfunction "2_2") (pintype "passive"))
      (node (ref "R25") (pin "2") (pinfunction "2_2") (pintype "passive"))
      (node (ref "TP17") (pin "1") (pinfunction "G9_1") (pintype "passive"))
    )
    (net (code "28") (name "GNDISO_B") (class "Default")
      (node (ref "C1") (pin "1") (pinfunction "1_1") (pintype "passive"))
      (node (ref "C14") (pin "1") (pinfunction "1_1") (pintype "passive"))
      (node (ref "C15") (pin "1") (pinfunction "1_1") (pintype "passive"))
      (node (ref "C18") (pin "1") (pinfunction "1_1") (pintype "passive"))
      (node (ref "C2") (pin "1") (pinfunction "1_1") (pintype "passive"))
      (node (ref "C21") (pin "1") (pinfunction "1_1") (pintype "passive"))
      (node (ref "C23") (pin "1") (pinfunction "1_1") (pintype "passive"))
      (node (ref "C27") (pin "1") (pinfunction "1_1") (pintype "passive"))
      (node (ref "C32") (pin "1") (pinfunction "1_1") (pintype "passive"))
      (node (ref "C33") (pin "1") (pinfunction "1_1") (pintype "passive"))
      (node (ref "C9") (pin "1") (pinfunction "1_1") (pintype "passive"))
      (node (ref "DD3") (pin "10") (pinfunction "GNDISO_10") (pintype "passive"))
      (node (ref "DD3") (pin "2") (pinfunction "GNDISO_2") (pintype "passive"))
      (node (ref "R19") (pin "2") (pinfunction "2_2") (pintype "passive"))
      (node (ref "R20") (pin "2") (pinfunction "2_2") (pintype "passive"))
      (node (ref "R27") (pin "2") (pinfunction "2_2") (pintype "passive"))
      (node (ref "TP19") (pin "1") (pinfunction "G9_1") (pintype "passive"))
    )
    (net (code "29") (name "GNDISO_C") (class "Default")
      (node (ref "C12") (pin "1") (pinfunction "1_1") (pintype "passive"))
      (node (ref "C13") (pin "1") (pinfunction "1_1") (pintype "passive"))
      (node (ref "C17") (pin "1") (pinfunction "1_1") (pintype "passive"))
      (node (ref "C20") (pin "1") (pinfunction "1_1") (pintype "passive"))
      (node (ref "C22") (pin "1") (pinfunction "1_1") (pintype "passive"))
      (node (ref "C26") (pin "1") (pinfunction "1_1") (pintype "passive"))
      (node (ref "C30") (pin "1") (pinfunction "1_1") (pintype "passive"))
      (node (ref "C31") (pin "1") (pinfunction "1_1") (pintype "passive"))
      (node (ref "C5") (pin "1") (pinfunction "1_1") (pintype "passive"))
      (node (ref "C6") (pin "1") (pinfunction "1_1") (pintype "passive"))
      (node (ref "C8") (pin "1") (pinfunction "1_1") (pintype "passive"))
      (node (ref "DD2") (pin "10") (pinfunction "GNDISO_10") (pintype "passive"))
      (node (ref "DD2") (pin "2") (pinfunction "GNDISO_2") (pintype "passive"))
      (node (ref "R23") (pin "2") (pinfunction "2_2") (pintype "passive"))
      (node (ref "R24") (pin "2") (pinfunction "2_2") (pintype "passive"))
      (node (ref "R26") (pin "2") (pinfunction "2_2") (pintype "passive"))
      (node (ref "TP18") (pin "1") (pinfunction "G9_1") (pintype "passive"))
    )
    (net (code "30") (name "NEUTRAL") (class "Default")
      (node (ref "DD4") (pin "1") (pinfunction "AC/N_1") (pintype "passive"))
      (node (ref "R2") (pin "2") (pinfunction "2_2") (pintype "passive"))
      (node (ref "R4") (pin "2") (pinfunction "2_2") (pintype "passive"))
      (node (ref "R6") (pin "2") (pinfunction "2_2") (pintype "passive"))
      (node (ref "TP1") (pin "1") (pinfunction "G9_1") (pintype "passive"))
      (node (ref "X5") (pin "5") (pinfunction "5_5") (pintype "passive"))
    )
    (net (code "31") (name "Net-(DD1-IM)") (class "Default")
      (node (ref "C10") (pin "2") (pinfunction "2_2") (pintype "passive"))
      (node (ref "DD1") (pin "6") (pinfunction "IM_6") (pintype "passive"))
      (node (ref "R34") (pin "1") (pinfunction "1_1") (pintype "passive"))
      (node (ref "TP14") (pin "1") (pinfunction "G9_1") (pintype "passive"))
      (node (ref "VD27") (pin "1") (pinfunction "C_1") (pintype "passive"))
      (node (ref "VD30") (pin "2") (pinfunction "A_2") (pintype "passive"))
    )
    (net (code "32") (name "Net-(DD1-IP)") (class "Default")
      (node (ref "C11") (pin "2") (pinfunction "2_2") (pintype "passive"))
      (node (ref "DD1") (pin "7") (pinfunction "IP_7") (pintype "passive"))
      (node (ref "R35") (pin "1") (pinfunction "1_1") (pintype "passive"))
      (node (ref "TP15") (pin "1") (pinfunction "G9_1") (pintype "passive"))
      (node (ref "VD27") (pin "2") (pinfunction "A_2") (pintype "passive"))
      (node (ref "VD30") (pin "1") (pinfunction "C_1") (pintype "passive"))
    )
    (net (code "33") (name "Net-(DD1-LDO)") (class "Default")
      (node (ref "C16") (pin "2") (pinfunction "2_2") (pintype "passive"))
      (node (ref "C19") (pin "2") (pinfunction "2_2") (pintype "passive"))
      (node (ref "DD1") (pin "8") (pinfunction "LDO_8") (pintype "passive"))
    )
    (net (code "34") (name "Net-(DD1-REF)") (class "Default")
      (node (ref "C25") (pin "2") (pinfunction "2_2") (pintype "passive"))
      (node (ref "C29") (pin "2") (pinfunction "2_2") (pintype "passive"))
      (node (ref "DD1") (pin "9") (pinfunction "REF_9") (pintype "passive"))
    )
    (net (code "35") (name "Net-(DD1-VDDISO)") (class "Default")
      (node (ref "C24") (pin "2") (pinfunction "2_2") (pintype "passive"))
      (node (ref "C28") (pin "2") (pinfunction "2_2") (pintype "passive"))
      (node (ref "DD1") (pin "1") (pinfunction "VDDISO_1") (pintype "passive"))
      (node (ref "TP22") (pin "1") (pinfunction "G9_1") (pintype "passive"))
    )
    (net (code "36") (name "Net-(DD1-XTAL1)") (class "Default")
      (node (ref "DD1") (pin "13") (pinfunction "XTAL1_13") (pintype "passive"))
      (node (ref "DD2") (pin "13") (pinfunction "XTAL1_13") (pintype "passive"))
      (node (ref "DD3") (pin "12") (pinfunction "CLKOUT/DREADY_12") (pintype "passive"))
    )
    (net (code "37") (name "Net-(DD2-IM)") (class "Default")
      (node (ref "C12") (pin "2") (pinfunction "2_2") (pintype "passive"))
      (node (ref "DD2") (pin "6") (pinfunction "IM_6") (pintype "passive"))
      (node (ref "R36") (pin "1") (pinfunction "1_1") (pintype "passive"))
      (node (ref "TP16") (pin "1") (pinfunction "G9_1") (pintype "passive"))
      (node (ref "VD25") (pin "1") (pinfunction "C_1") (pintype "passive"))
      (node (ref "VD28") (pin "2") (pinfunction "A_2") (pintype "passive"))
    )
    (net (code "38") (name "Net-(DD2-IP)") (class "Default")
      (node (ref "C13") (pin "2") (pinfunction "2_2") (pintype "passive"))
      (node (ref "DD2") (pin "7") (pinfunction "IP_7") (pintype "passive"))
      (node (ref "R37") (pin "1") (pinfunction "1_1") (pintype "passive"))
      (node (ref "TP11") (pin "1") (pinfunction "G9_1") (pintype "passive"))
      (node (ref "VD25") (pin "2") (pinfunction "A_2") (pintype "passive"))
      (node (ref "VD28") (pin "1") (pinfunction "C_1") (pintype "passive"))
    )
    (net (code "39") (name "Net-(DD2-LDO)") (class "Default")
      (node (ref "C17") (pin "2") (pinfunction "2_2") (pintype "passive"))
      (node (ref "C20") (pin "2") (pinfunction "2_2") (pintype "passive"))
      (node (ref "DD2") (pin "8") (pinfunction "LDO_8") (pintype "passive"))
    )
    (net (code "40") (name "Net-(DD2-REF)") (class "Default")
      (node (ref "C26") (pin "2") (pinfunction "2_2") (pintype "passive"))
      (node (ref "C31") (pin "2") (pinfunction "2_2") (pintype "passive"))
      (node (ref "DD2") (pin "9") (pinfunction "REF_9") (pintype "passive"))
    )
    (net (code "41") (name "Net-(DD2-VDDISO)") (class "Default")
      (node (ref "C22") (pin "2") (pinfunction "2_2") (pintype "passive"))
      (node (ref "C30") (pin "2") (pinfunction "2_2") (pintype "passive"))
      (node (ref "DD2") (pin "1") (pinfunction "VDDISO_1") (pintype "passive"))
      (node (ref "TP21") (pin "1") (pinfunction "G9_1") (pintype "passive"))
    )
    (net (code "42") (name "Net-(DD3-IM)") (class "Default")
      (node (ref "C14") (pin "2") (pinfunction "2_2") (pintype "passive"))
      (node (ref "DD3") (pin "6") (pinfunction "IM_6") (pintype "passive"))
      (node (ref "R38") (pin "1") (pinfunction "1_1") (pintype "passive"))
      (node (ref "TP12") (pin "1") (pinfunction "G9_1") (pintype "passive"))
      (node (ref "VD26") (pin "1") (pinfunction "C_1") (pintype "passive"))
      (node (ref "VD29") (pin "2") (pinfunction "A_2") (pintype "passive"))
    )
    (net (code "43") (name "Net-(DD3-IP)") (class "Default")
      (node (ref "C15") (pin "2") (pinfunction "2_2") (pintype "passive"))
      (node (ref "DD3") (pin "7") (pinfunction "IP_7") (pintype "passive"))
      (node (ref "R39") (pin "1") (pinfunction "1_1") (pintype "passive"))
      (node (ref "TP13") (pin "1") (pinfunction "G9_1") (pintype "passive"))
      (node (ref "VD26") (pin "2") (pinfunction "A_2") (pintype "passive"))
      (node (ref "VD29") (pin "1") (pinfunction "C_1") (pintype "passive"))
    )
    (net (code "44") (name "Net-(DD3-LDO)") (class "Default")
      (node (ref "C18") (pin "2") (pinfunction "2_2") (pintype "passive"))
      (node (ref "C21") (pin "2") (pinfunction "2_2") (pintype "passive"))
      (node (ref "DD3") (pin "8") (pinfunction "LDO_8") (pintype "passive"))
    )
    (net (code "45") (name "Net-(DD3-REF)") (class "Default")
      (node (ref "C27") (pin "2") (pinfunction "2_2") (pintype "passive"))
      (node (ref "C33") (pin "2") (pinfunction "2_2") (pintype "passive"))
      (node (ref "DD3") (pin "9") (pinfunction "REF_9") (pintype "passive"))
    )
    (net (code "46") (name "Net-(DD3-VDDISO)") (class "Default")
      (node (ref "C23") (pin "2") (pinfunction "2_2") (pintype "passive"))
      (node (ref "C32") (pin "2") (pinfunction "2_2") (pintype "passive"))
      (node (ref "DD3") (pin "1") (pinfunction "VDDISO_1") (pintype "passive"))
      (node (ref "TP20") (pin "1") (pinfunction "G9_1") (pintype "passive"))
    )
    (net (code "47") (name "Net-(DD3-XTAL1)") (class "Default")
      (node (ref "C34") (pin "2") (pinfunction "2_2") (pintype "passive"))
      (node (ref "DD3") (pin "13") (pinfunction "XTAL1_13") (pintype "passive"))
      (node (ref "Q1") (pin "1") (pinfunction "1_1") (pintype "passive"))
    )
    (net (code "48") (name "Net-(DD3-XTAL2)") (class "Default")
      (node (ref "C35") (pin "2") (pinfunction "2_2") (pintype "passive"))
      (node (ref "DD3") (pin "14") (pinfunction "XTAL2_14") (pintype "passive"))
      (node (ref "Q1") (pin "2") (pinfunction "2_2") (pintype "passive"))
    )
    (net (code "49") (name "Net-(R1-Pad1)") (class "Default")
      (node (ref "R1") (pin "1") (pinfunction "1_1") (pintype "passive"))
      (node (ref "R7") (pin "2") (pinfunction "2_2") (pintype "passive"))
    )
    (net (code "50") (name "Net-(R2-Pad1)") (class "Default")
      (node (ref "R2") (pin "1") (pinfunction "1_1") (pintype "passive"))
      (node (ref "R8") (pin "2") (pinfunction "2_2") (pintype "passive"))
    )
    (net (code "51") (name "Net-(R3-Pad1)") (class "Default")
      (node (ref "R3") (pin "1") (pinfunction "1_1") (pintype "passive"))
      (node (ref "R9") (pin "2") (pinfunction "2_2") (pintype "passive"))
    )
    (net (code "52") (name "Net-(R10-Pad1)") (class "Default")
      (node (ref "R10") (pin "1") (pinfunction "1_1") (pintype "passive"))
      (node (ref "R16") (pin "2") (pinfunction "2_2") (pintype "passive"))
    )
    (net (code "53") (name "Net-(R10-Pad2)") (class "Default")
      (node (ref "R10") (pin "2") (pinfunction "2_2") (pintype "passive"))
      (node (ref "R4") (pin "1") (pinfunction "1_1") (pintype "passive"))
    )
    (net (code "54") (name "Net-(R11-Pad1)") (class "Default")
      (node (ref "R11") (pin "1") (pinfunction "1_1") (pintype "passive"))
      (node (ref "R17") (pin "2") (pinfunction "2_2") (pintype "passive"))
    )
    (net (code "55") (name "Net-(R11-Pad2)") (class "Default")
      (node (ref "R11") (pin "2") (pinfunction "2_2") (pintype "passive"))
      (node (ref "R5") (pin "1") (pinfunction "1_1") (pintype "passive"))
    )
    (net (code "56") (name "Net-(R12-Pad1)") (class "Default")
      (node (ref "R12") (pin "1") (pinfunction "1_1") (pintype "passive"))
      (node (ref "R18") (pin "2") (pinfunction "2_2") (pintype "passive"))
    )
    (net (code "57") (name "Net-(R12-Pad2)") (class "Default")
      (node (ref "R12") (pin "2") (pinfunction "2_2") (pintype "passive"))
      (node (ref "R6") (pin "1") (pinfunction "1_1") (pintype "passive"))
    )
    (net (code "58") (name "Net-(R13-Pad2)") (class "Default")
      (node (ref "R13") (pin "2") (pinfunction "2_2") (pintype "passive"))
      (node (ref "R7") (pin "1") (pinfunction "1_1") (pintype "passive"))
    )
    (net (code "59") (name "Net-(R14-Pad2)") (class "Default")
      (node (ref "R14") (pin "2") (pinfunction "2_2") (pintype "passive"))
      (node (ref "R8") (pin "1") (pinfunction "1_1") (pintype "passive"))
    )
    (net (code "60") (name "Net-(R15-Pad2)") (class "Default")
      (node (ref "R15") (pin "2") (pinfunction "2_2") (pintype "passive"))
      (node (ref "R9") (pin "1") (pinfunction "1_1") (pintype "passive"))
    )
    (net (code "61") (name "Net-(VD1-C)") (class "Default")
      (node (ref "VD1") (pin "1") (pinfunction "C_1") (pintype "passive"))
      (node (ref "VD2") (pin "2") (pinfunction "A_2") (pintype "passive"))
    )
    (net (code "62") (name "Net-(VD3-C)") (class "Default")
      (node (ref "VD3") (pin "1") (pinfunction "C_1") (pintype "passive"))
      (node (ref "VD4") (pin "2") (pinfunction "A_2") (pintype "passive"))
    )
    (net (code "63") (name "Net-(VD5-C)") (class "Default")
      (node (ref "VD5") (pin "1") (pinfunction "C_1") (pintype "passive"))
      (node (ref "VD6") (pin "2") (pinfunction "A_2") (pintype "passive"))
    )
    (net (code "64") (name "Net-(VD7-C)") (class "Default")
      (node (ref "VD7") (pin "1") (pinfunction "C_1") (pintype "passive"))
      (node (ref "VD8") (pin "2") (pinfunction "A_2") (pintype "passive"))
    )
    (net (code "65") (name "Net-(VD10-A)") (class "Default")
      (node (ref "VD10") (pin "2") (pinfunction "A_2") (pintype "passive"))
      (node (ref "VD9") (pin "1") (pinfunction "C_1") (pintype "passive"))
    )
    (net (code "66") (name "Net-(VD11-C)") (class "Default")
      (node (ref "VD11") (pin "1") (pinfunction "C_1") (pintype "passive"))
      (node (ref "VD12") (pin "2") (pinfunction "A_2") (pintype "passive"))
    )
    (net (code "67") (name "Net-(VD13-A)") (class "Default")
      (node (ref "VD13") (pin "2") (pinfunction "A_2") (pintype "passive"))
      (node (ref "VD14") (pin "1") (pinfunction "C_1") (pintype "passive"))
    )
    (net (code "68") (name "Net-(VD15-A)") (class "Default")
      (node (ref "VD15") (pin "2") (pinfunction "A_2") (pintype "passive"))
      (node (ref "VD16") (pin "1") (pinfunction "C_1") (pintype "passive"))
    )
    (net (code "69") (name "Net-(VD17-A)") (class "Default")
      (node (ref "VD17") (pin "2") (pinfunction "A_2") (pintype "passive"))
      (node (ref "VD18") (pin "1") (pinfunction "C_1") (pintype "passive"))
    )
    (net (code "70") (name "Net-(VD19-A)") (class "Default")
      (node (ref "VD19") (pin "2") (pinfunction "A_2") (pintype "passive"))
      (node (ref "VD20") (pin "1") (pinfunction "C_1") (pintype "passive"))
    )
    (net (code "71") (name "Net-(VD21-A)") (class "Default")
      (node (ref "VD21") (pin "2") (pinfunction "A_2") (pintype "passive"))
      (node (ref "VD22") (pin "1") (pinfunction "C_1") (pintype "passive"))
    )
    (net (code "72") (name "Net-(VD23-A)") (class "Default")
      (node (ref "VD23") (pin "2") (pinfunction "A_2") (pintype "passive"))
      (node (ref "VD24") (pin "1") (pinfunction "C_1") (pintype "passive"))
    )
    (net (code "73") (name "unconnected-(DD1-XTAL2-Pad14)") (class "Default")
      (node (ref "DD1") (pin "14") (pinfunction "XTAL2_14") (pintype "passive"))
    )
    (net (code "74") (name "unconnected-(DD2-CLKOUT{slash}DREADY-Pad12)") (class "Default")
      (node (ref "DD2") (pin "12") (pinfunction "CLKOUT/DREADY_12") (pintype "passive"))
    )
    (net (code "75") (name "unconnected-(DD2-XTAL2-Pad14)") (class "Default")
      (node (ref "DD2") (pin "14") (pinfunction "XTAL2_14") (pintype "passive"))
    )
    (net (code "76") (name "unconnected-(X3-Pad1)") (class "Default")
      (node (ref "X3") (pin "1") (pinfunction "1_1") (pintype "passive"))
    )
    (net (code "77") (name "unconnected-(X3-Pad2)") (class "Default")
      (node (ref "X3") (pin "2") (pinfunction "2_2") (pintype "passive"))
    )
    (net (code "78") (name "unconnected-(X3-Pad4)") (class "Default")
      (node (ref "X3") (pin "4") (pinfunction "4_4") (pintype "passive"))
    )
    (net (code "79") (name "unconnected-(X3-Pad5)") (class "Default")
      (node (ref "X3") (pin "5") (pinfunction "5_5") (pintype "passive"))
    )
    (net (code "80") (name "unconnected-(X4-Pad3)") (class "Default")
      (node (ref "X4") (pin "3") (pinfunction "3_3") (pintype "passive"))
    )
    (net (code "81") (name "unconnected-(X5-Pad1)") (class "Default")
      (node (ref "X5") (pin "1") (pinfunction "1_1") (pintype "passive"))
    )
    (net (code "82") (name "unconnected-(X5-Pad4)") (class "Default")
      (node (ref "X5") (pin "4") (pinfunction "4_4") (pintype "passive"))
    )
  )
)
